# MS_Electron_SC.net
KiCad netlist of a schematic drawn in EAGLE
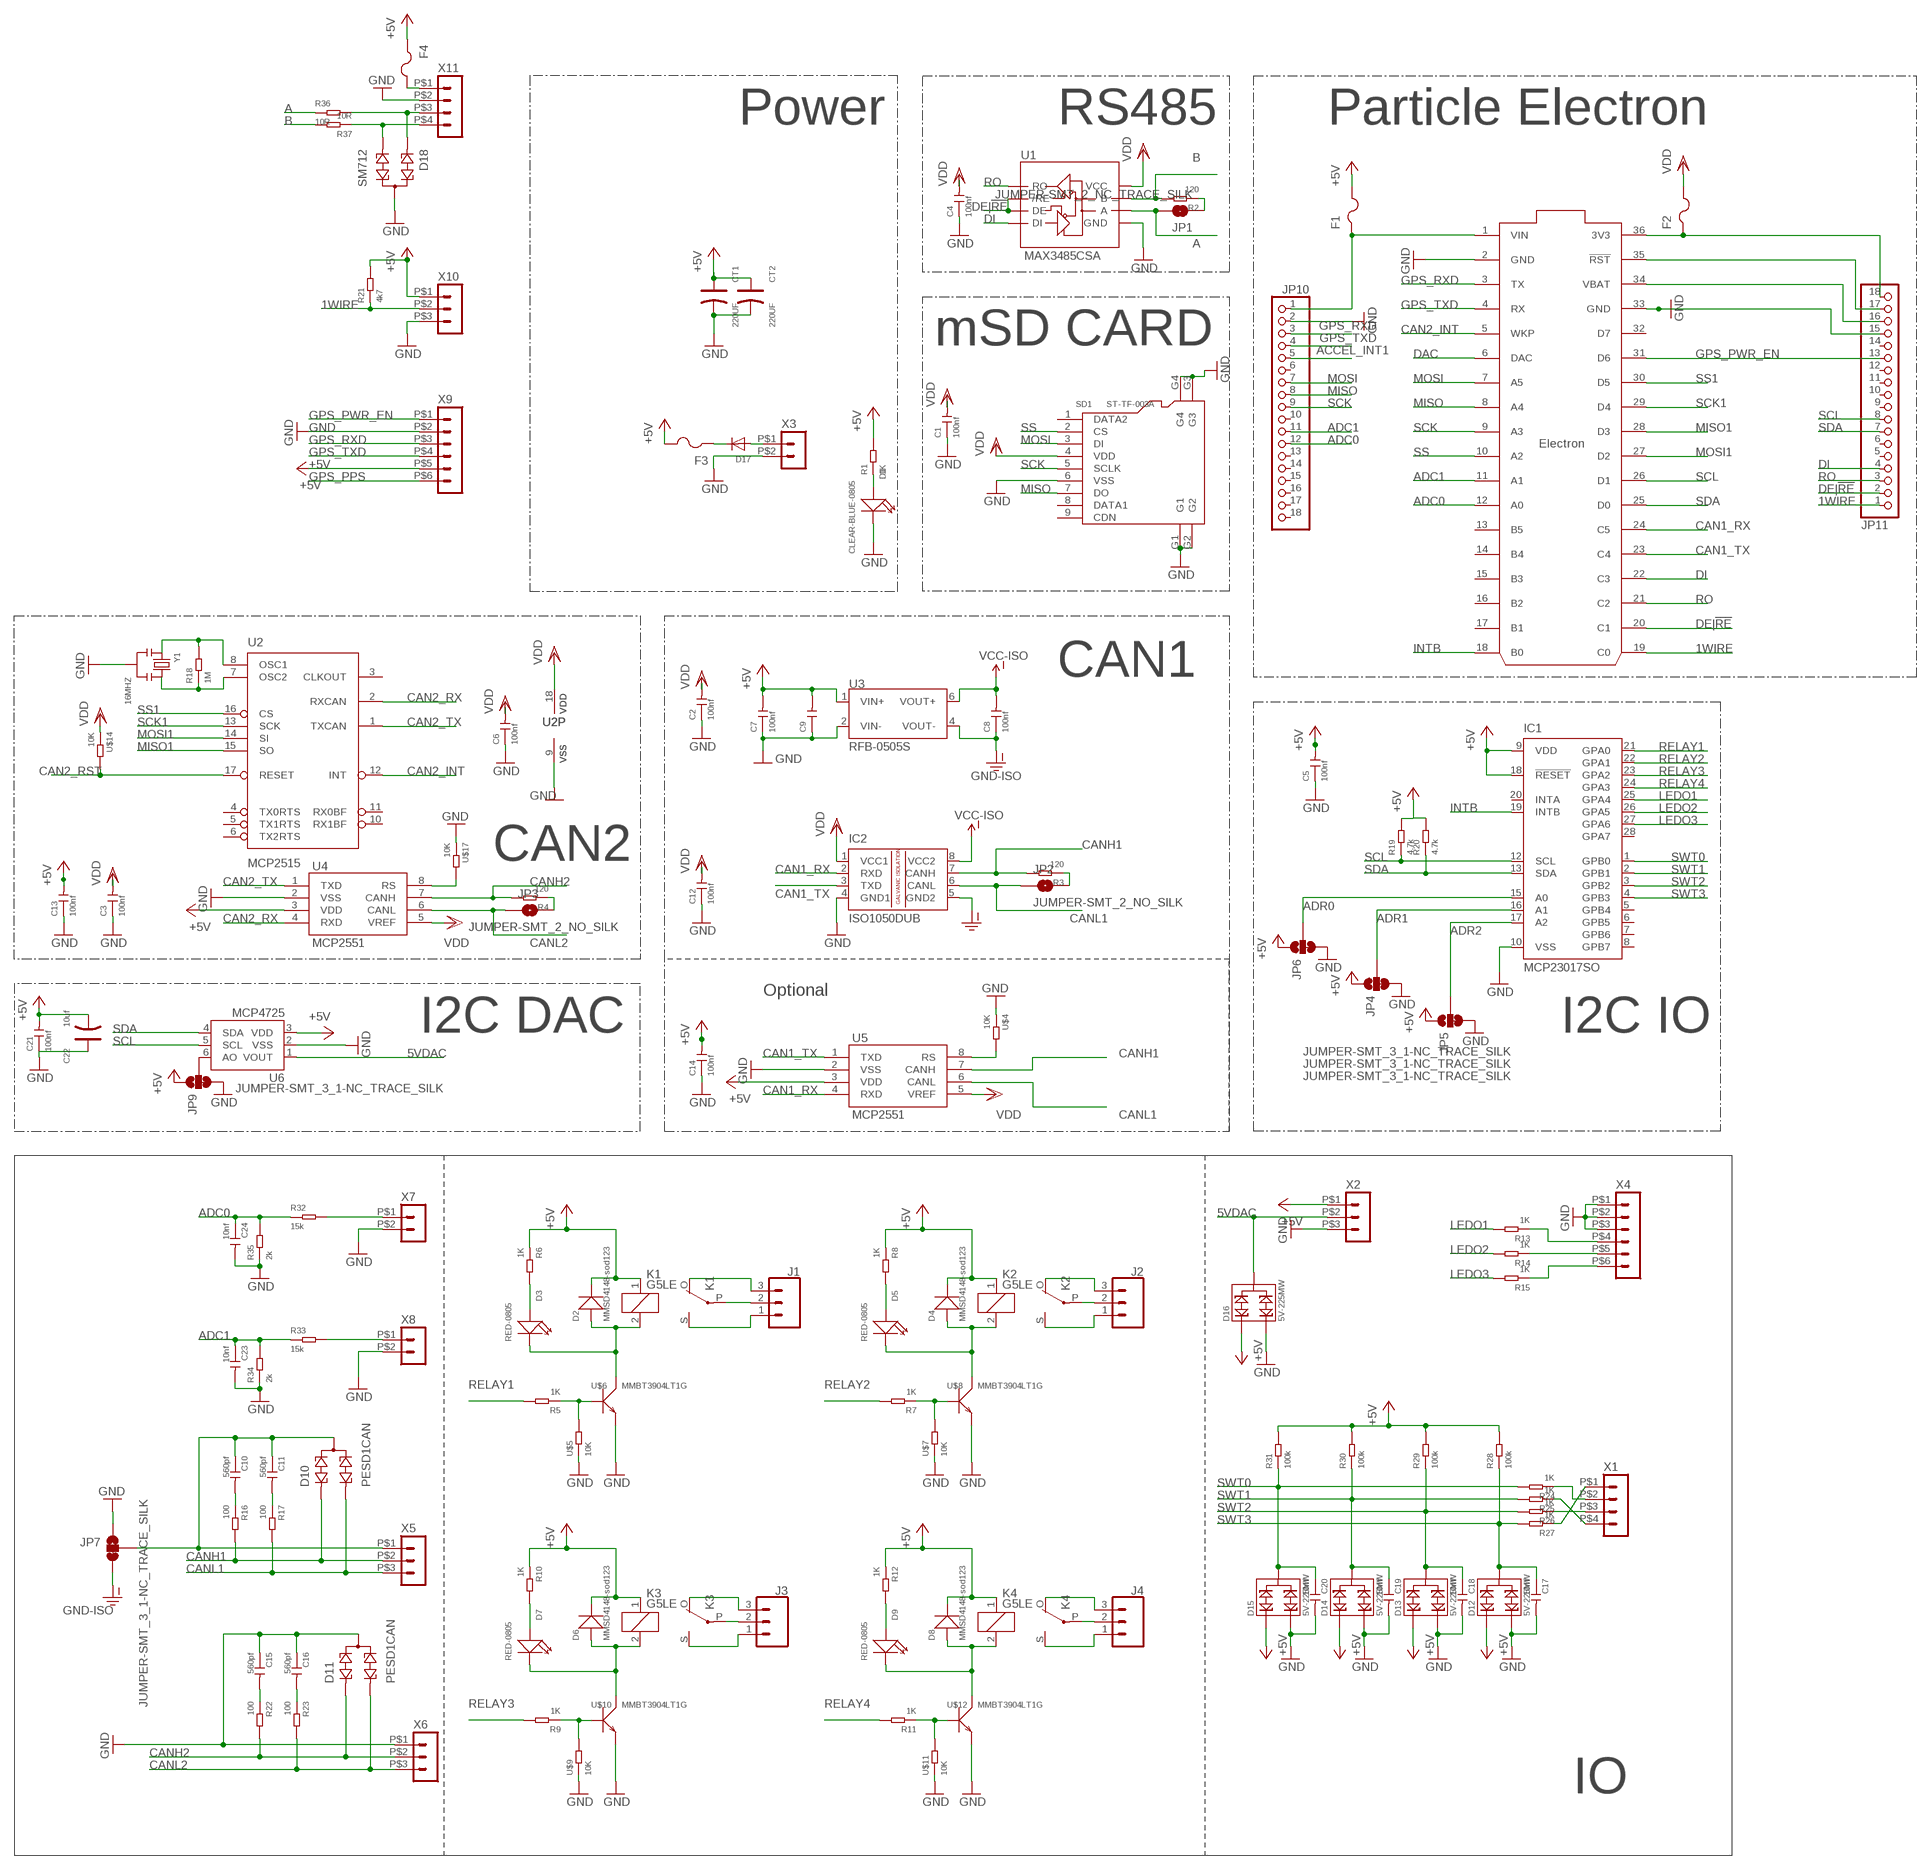
[diagram p0: schematic, sheet 1]

(export (version "E")
  (design (tool "Eeschema 10.0.6"))
  (components
    (comp (ref "C1")
      (value "100nf")
      (footprint "eagle-import:C0805")
      (fields (field (name "MPN") "CC0805KRX7R9BB104"))
      (libsource (lib "eagle-import") (part "CERAMIC-100NF-50V-10%-X7R(0805)"))
    )
    (comp (ref "C2")
      (value "100nf")
      (footprint "eagle-import:C0805")
      (fields (field (name "MPN") "CC0805KRX7R9BB104"))
      (libsource (lib "eagle-import") (part "CERAMIC-100NF-50V-10%-X7R(0805)"))
    )
    (comp (ref "C3")
      (value "100nf")
      (footprint "eagle-import:C0805")
      (fields (field (name "MPN") "CC0805KRX7R9BB104"))
      (libsource (lib "eagle-import") (part "CERAMIC-100NF-50V-10%-X7R(0805)"))
    )
    (comp (ref "C4")
      (value "100nf")
      (footprint "eagle-import:C0805")
      (fields (field (name "MPN") "CC0805KRX7R9BB104"))
      (libsource (lib "eagle-import") (part "CERAMIC-100NF-50V-10%-X7R(0805)"))
    )
    (comp (ref "C5")
      (value "100nf")
      (footprint "eagle-import:C0805")
      (fields (field (name "MPN") "CC0805KRX7R9BB104"))
      (libsource (lib "eagle-import") (part "CERAMIC-100NF-50V-10%-X7R(0805)"))
    )
    (comp (ref "C6")
      (value "100nf")
      (footprint "eagle-import:C0805")
      (fields (field (name "MPN") "CC0805KRX7R9BB104"))
      (libsource (lib "eagle-import") (part "CERAMIC-100NF-50V-10%-X7R(0805)"))
    )
    (comp (ref "C7")
      (value "100nf")
      (footprint "eagle-import:C0805")
      (fields (field (name "MPN") "CC0805KRX7R9BB104"))
      (libsource (lib "eagle-import") (part "CERAMIC-100NF-50V-10%-X7R(0805)"))
    )
    (comp (ref "C8")
      (value "100nf")
      (footprint "eagle-import:C0805")
      (fields (field (name "MPN") "CC0805KRX7R9BB104"))
      (libsource (lib "eagle-import") (part "CERAMIC-100NF-50V-10%-X7R(0805)"))
    )
    (comp (ref "C9")
      (value "CERAMIC-22UF-16V-10%-X7R(1206)")
      (footprint "eagle-import:C1206")
      (libsource (lib "eagle-import") (part "CERAMIC-22UF-16V-10%-X7R(1206)"))
    )
    (comp (ref "C10")
      (value "560pf")
      (footprint "eagle-import:C0805")
      (fields (field (name "MPN") "CC0805JRX7R9BB103"))
      (libsource (lib "eagle-import") (part "CERAMIC-10NF-50V-5%-X7R(0805)"))
    )
    (comp (ref "C11")
      (value "560pf")
      (footprint "eagle-import:C0805")
      (fields (field (name "MPN") "CC0805JRX7R9BB103"))
      (libsource (lib "eagle-import") (part "CERAMIC-10NF-50V-5%-X7R(0805)"))
    )
    (comp (ref "C12")
      (value "100nf")
      (footprint "eagle-import:C0805")
      (fields (field (name "MPN") "CC0805KRX7R9BB104"))
      (libsource (lib "eagle-import") (part "CERAMIC-100NF-50V-10%-X7R(0805)"))
    )
    (comp (ref "C13")
      (value "100nf")
      (footprint "eagle-import:C0805")
      (fields (field (name "MPN") "CC0805KRX7R9BB104"))
      (libsource (lib "eagle-import") (part "CERAMIC-100NF-50V-10%-X7R(0805)"))
    )
    (comp (ref "C14")
      (value "100nf")
      (footprint "eagle-import:C0805")
      (fields (field (name "MPN") "CC0805KRX7R9BB104"))
      (libsource (lib "eagle-import") (part "CERAMIC-100NF-50V-10%-X7R(0805)"))
    )
    (comp (ref "C15")
      (value "560pf")
      (footprint "eagle-import:C0805")
      (fields (field (name "MPN") "CC0805JRX7R9BB103"))
      (libsource (lib "eagle-import") (part "CERAMIC-10NF-50V-5%-X7R(0805)"))
    )
    (comp (ref "C16")
      (value "560pf")
      (footprint "eagle-import:C0805")
      (fields (field (name "MPN") "CC0805JRX7R9BB103"))
      (libsource (lib "eagle-import") (part "CERAMIC-10NF-50V-5%-X7R(0805)"))
    )
    (comp (ref "C17")
      (value "10nf")
      (footprint "eagle-import:C0805")
      (fields (field (name "MPN") "CC0805JRX7R9BB103"))
      (libsource (lib "eagle-import") (part "CERAMIC-10NF-50V-5%-X7R(0805)"))
    )
    (comp (ref "C18")
      (value "10nf")
      (footprint "eagle-import:C0805")
      (fields (field (name "MPN") "CC0805JRX7R9BB103"))
      (libsource (lib "eagle-import") (part "CERAMIC-10NF-50V-5%-X7R(0805)"))
    )
    (comp (ref "C19")
      (value "10nf")
      (footprint "eagle-import:C0805")
      (fields (field (name "MPN") "CC0805JRX7R9BB103"))
      (libsource (lib "eagle-import") (part "CERAMIC-10NF-50V-5%-X7R(0805)"))
    )
    (comp (ref "C20")
      (value "10nf")
      (footprint "eagle-import:C0805")
      (fields (field (name "MPN") "CC0805JRX7R9BB103"))
      (libsource (lib "eagle-import") (part "CERAMIC-10NF-50V-5%-X7R(0805)"))
    )
    (comp (ref "C21")
      (value "100nf")
      (footprint "eagle-import:C0805")
      (fields (field (name "MPN") "CC0805KRX7R9BB104"))
      (libsource (lib "eagle-import") (part "CERAMIC-100NF-50V-10%-X7R(0805)"))
    )
    (comp (ref "C22")
      (value "10uf")
      (footprint "eagle-import:AVX-A")
      (fields (field (name "MPN") "TAJA106K010RNJ"))
      (libsource (lib "eagle-import") (part "TANTALUM-SMD-10UF-10V-10%(AVX-A)"))
    )
    (comp (ref "C23")
      (value "10nf")
      (footprint "eagle-import:C0805")
      (fields (field (name "MPN") "CC0805JRX7R9BB103"))
      (libsource (lib "eagle-import") (part "CERAMIC-10NF-50V-5%-X7R(0805)"))
    )
    (comp (ref "C24")
      (value "10nf")
      (footprint "eagle-import:C0805")
      (fields (field (name "MPN") "CC0805JRX7R9BB103"))
      (libsource (lib "eagle-import") (part "CERAMIC-10NF-50V-5%-X7R(0805)"))
    )
    (comp (ref "CT1")
      (value "220UF")
      (footprint "eagle-import:ELECTRO-SMD-C-6MM")
      (fields (field (name "MPN") "CS1E221M-CRE77"))
      (libsource (lib "eagle-import") (part "ALUMINUM-SMD-220UF-16V(D6.3-H7.7MM)"))
    )
    (comp (ref "CT2")
      (value "220UF")
      (footprint "eagle-import:ELECTRO-SMD-C-6MM")
      (fields (field (name "MPN") "CS1E221M-CRE77"))
      (libsource (lib "eagle-import") (part "ALUMINUM-SMD-220UF-16V(D6.3-H7.7MM)"))
    )
    (comp (ref "D1")
      (value "CLEAR-BLUE-0805")
      (footprint "eagle-import:LED-0805")
      (fields (field (name "MPN") "EL-17-215/BHC-AN1P2/3T"))
      (libsource (lib "eagle-import") (part "SMD-LED-CLEAR-BLUE(0805)"))
    )
    (comp (ref "D2")
      (value "MMSD4148-sod123")
      (footprint "eagle-import:SOD-123")
      (fields (field (name "MPN") "MMSD4148"))
      (libsource (lib "eagle-import") (part "SMD-DIODE-100V-200MA(SOD-123)"))
    )
    (comp (ref "D3")
      (value "RED-0805")
      (footprint "eagle-import:LED-0805")
      (fields (field (name "MPN") "17-215SURC/S530-A2/TR8"))
      (libsource (lib "eagle-import") (part "SMD-LED-CLEAR-RED(0805)"))
    )
    (comp (ref "D4")
      (value "MMSD4148-sod123")
      (footprint "eagle-import:SOD-123")
      (fields (field (name "MPN") "MMSD4148"))
      (libsource (lib "eagle-import") (part "SMD-DIODE-100V-200MA(SOD-123)"))
    )
    (comp (ref "D5")
      (value "RED-0805")
      (footprint "eagle-import:LED-0805")
      (fields (field (name "MPN") "17-215SURC/S530-A2/TR8"))
      (libsource (lib "eagle-import") (part "SMD-LED-CLEAR-RED(0805)"))
    )
    (comp (ref "D6")
      (value "MMSD4148-sod123")
      (footprint "eagle-import:SOD-123")
      (fields (field (name "MPN") "MMSD4148"))
      (libsource (lib "eagle-import") (part "SMD-DIODE-100V-200MA(SOD-123)"))
    )
    (comp (ref "D7")
      (value "RED-0805")
      (footprint "eagle-import:LED-0805")
      (fields (field (name "MPN") "17-215SURC/S530-A2/TR8"))
      (libsource (lib "eagle-import") (part "SMD-LED-CLEAR-RED(0805)"))
    )
    (comp (ref "D8")
      (value "MMSD4148-sod123")
      (footprint "eagle-import:SOD-123")
      (fields (field (name "MPN") "MMSD4148"))
      (libsource (lib "eagle-import") (part "SMD-DIODE-100V-200MA(SOD-123)"))
    )
    (comp (ref "D9")
      (value "RED-0805")
      (footprint "eagle-import:LED-0805")
      (fields (field (name "MPN") "17-215SURC/S530-A2/TR8"))
      (libsource (lib "eagle-import") (part "SMD-LED-CLEAR-RED(0805)"))
    )
    (comp (ref "D10")
      (value "PESD1CAN")
      (footprint "eagle-import:SOT23")
      (libsource (lib "eagle-import") (part "PESD1CAN"))
    )
    (comp (ref "D11")
      (value "PESD1CAN")
      (footprint "eagle-import:SOT23")
      (libsource (lib "eagle-import") (part "PESD1CAN"))
    )
    (comp (ref "D12")
      (value "5V-225MW")
      (footprint "eagle-import:SOT-23")
      (fields (field (name "MPN") "CESD5V0AP"))
      (libsource (lib "eagle-import") (part "SMD-DIODE-TVS-5V-225MW(SOT-23)"))
    )
    (comp (ref "D13")
      (value "5V-225MW")
      (footprint "eagle-import:SOT-23")
      (fields (field (name "MPN") "CESD5V0AP"))
      (libsource (lib "eagle-import") (part "SMD-DIODE-TVS-5V-225MW(SOT-23)"))
    )
    (comp (ref "D14")
      (value "5V-225MW")
      (footprint "eagle-import:SOT-23")
      (fields (field (name "MPN") "CESD5V0AP"))
      (libsource (lib "eagle-import") (part "SMD-DIODE-TVS-5V-225MW(SOT-23)"))
    )
    (comp (ref "D15")
      (value "5V-225MW")
      (footprint "eagle-import:SOT-23")
      (fields (field (name "MPN") "CESD5V0AP"))
      (libsource (lib "eagle-import") (part "SMD-DIODE-TVS-5V-225MW(SOT-23)"))
    )
    (comp (ref "D16")
      (value "5V-225MW")
      (footprint "eagle-import:SOT-23")
      (fields (field (name "MPN") "CESD5V0AP"))
      (libsource (lib "eagle-import") (part "SMD-DIODE-TVS-5V-225MW(SOT-23)"))
    )
    (comp (ref "D17")
      (value "DIODESMA")
      (footprint "eagle-import:SMADIODE")
      (libsource (lib "eagle-import") (part "DIODESMA"))
    )
    (comp (ref "D18")
      (value "SM712")
      (footprint "eagle-import:SOT23")
      (libsource (lib "eagle-import") (part "PESD1CAN"))
    )
    (comp (ref "F1")
      (value "PTCFUSE-1812")
      (footprint "eagle-import:1812")
      (libsource (lib "eagle-import") (part "PTCFUSE-1812"))
    )
    (comp (ref "F2")
      (value "PTCFUSE-1812")
      (footprint "eagle-import:1812")
      (libsource (lib "eagle-import") (part "PTCFUSE-1812"))
    )
    (comp (ref "F3")
      (value "PTCFUSE-1812")
      (footprint "eagle-import:1812")
      (libsource (lib "eagle-import") (part "PTCFUSE-1812"))
    )
    (comp (ref "F4")
      (value "PTCFUSE-1812")
      (footprint "eagle-import:1812")
      (libsource (lib "eagle-import") (part "PTCFUSE-1812"))
    )
    (comp (ref "IC1")
      (value "MCP23017SO")
      (footprint "eagle-import:SO28W")
      (libsource (lib "eagle-import") (part "MCP23017SO"))
    )
    (comp (ref "IC2")
      (value "ISO1050DUB")
      (footprint "eagle-import:DUB-R-PDSO-G8")
      (fields (field (name "MPN") "ISO1050DUBR"))
      (libsource (lib "eagle-import") (part "ISO1050DUB"))
    )
    (comp (ref "J1")
      (value "CONN_03SCREW")
      (footprint "eagle-import:SCREWTERMINAL-3.5MM-3")
      (libsource (lib "eagle-import") (part "CONN_03SCREW"))
    )
    (comp (ref "J2")
      (value "CONN_03SCREW")
      (footprint "eagle-import:SCREWTERMINAL-3.5MM-3")
      (libsource (lib "eagle-import") (part "CONN_03SCREW"))
    )
    (comp (ref "J3")
      (value "CONN_03SCREW")
      (footprint "eagle-import:SCREWTERMINAL-3.5MM-3")
      (libsource (lib "eagle-import") (part "CONN_03SCREW"))
    )
    (comp (ref "J4")
      (value "CONN_03SCREW")
      (footprint "eagle-import:SCREWTERMINAL-3.5MM-3")
      (libsource (lib "eagle-import") (part "CONN_03SCREW"))
    )
    (comp (ref "JP1")
      (value "JUMPER-SMT_2_NC_TRACE_SILK")
      (footprint "eagle-import:SMT-JUMPER_2_NC_TRACE_SILK")
      (libsource (lib "eagle-import") (part "JUMPER-SMT_2_NC_TRACE_SILK"))
    )
    (comp (ref "JP2")
      (value "JUMPER-SMT_2_NO_SILK")
      (footprint "eagle-import:SMT-JUMPER_2_NO_SILK")
      (libsource (lib "eagle-import") (part "JUMPER-SMT_2_NO_SILK"))
    )
    (comp (ref "JP3")
      (value "JUMPER-SMT_2_NO_SILK")
      (footprint "eagle-import:SMT-JUMPER_2_NO_SILK")
      (libsource (lib "eagle-import") (part "JUMPER-SMT_2_NO_SILK"))
    )
    (comp (ref "JP4")
      (value "JUMPER-SMT_3_1-NC_TRACE_SILK")
      (footprint "eagle-import:SMT-JUMPER_3_1-NC_TRACE_SILK")
      (libsource (lib "eagle-import") (part "JUMPER-SMT_3_1-NC_TRACE_SILK"))
    )
    (comp (ref "JP5")
      (value "JUMPER-SMT_3_1-NC_TRACE_SILK")
      (footprint "eagle-import:SMT-JUMPER_3_1-NC_TRACE_SILK")
      (libsource (lib "eagle-import") (part "JUMPER-SMT_3_1-NC_TRACE_SILK"))
    )
    (comp (ref "JP6")
      (value "JUMPER-SMT_3_1-NC_TRACE_SILK")
      (footprint "eagle-import:SMT-JUMPER_3_1-NC_TRACE_SILK")
      (libsource (lib "eagle-import") (part "JUMPER-SMT_3_1-NC_TRACE_SILK"))
    )
    (comp (ref "JP7")
      (value "JUMPER-SMT_3_1-NC_TRACE_SILK")
      (footprint "eagle-import:SMT-JUMPER_3_1-NC_TRACE_SILK")
      (libsource (lib "eagle-import") (part "JUMPER-SMT_3_1-NC_TRACE_SILK"))
    )
    (comp (ref "JP9")
      (value "JUMPER-SMT_3_1-NC_TRACE_SILK")
      (footprint "eagle-import:SMT-JUMPER_3_1-NC_TRACE_SILK")
      (libsource (lib "eagle-import") (part "JUMPER-SMT_3_1-NC_TRACE_SILK"))
    )
    (comp (ref "JP10")
      (value "PINHD-1X18-BIG")
      (footprint "eagle-import:1X18-BIG")
      (libsource (lib "eagle-import") (part "PINHD-1X18-BIG"))
    )
    (comp (ref "JP11")
      (value "PINHD-1X18-BIG")
      (footprint "eagle-import:1X18-BIG")
      (libsource (lib "eagle-import") (part "PINHD-1X18-BIG"))
    )
    (comp (ref "K1")
      (value "G5LE")
      (footprint "eagle-import:G5LE")
      (libsource (lib "eagle-import") (part "G5LE"))
    )
    (comp (ref "K2")
      (value "G5LE")
      (footprint "eagle-import:G5LE")
      (libsource (lib "eagle-import") (part "G5LE"))
    )
    (comp (ref "K3")
      (value "G5LE")
      (footprint "eagle-import:G5LE")
      (libsource (lib "eagle-import") (part "G5LE"))
    )
    (comp (ref "K4")
      (value "G5LE")
      (footprint "eagle-import:G5LE")
      (libsource (lib "eagle-import") (part "G5LE"))
    )
    (comp (ref "R1")
      (value "1K")
      (footprint "eagle-import:R0805")
      (fields (field (name "MPN") "RC0805JR-071KL"))
      (libsource (lib "eagle-import") (part "SMD-RES-1K-5%-1/8W(0805)"))
    )
    (comp (ref "R2")
      (value "120")
      (footprint "eagle-import:R0805")
      (fields (field (name "MPN") "RC0805JR-071KL"))
      (libsource (lib "eagle-import") (part "SMD-RES-120R-1%-1/8W(0805)"))
    )
    (comp (ref "R3")
      (value "120")
      (footprint "eagle-import:R0805")
      (fields (field (name "MPN") "RC0805JR-071KL"))
      (libsource (lib "eagle-import") (part "SMD-RES-120R-1%-1/8W(0805)"))
    )
    (comp (ref "R4")
      (value "120")
      (footprint "eagle-import:R0805")
      (fields (field (name "MPN") "RC0805JR-071KL"))
      (libsource (lib "eagle-import") (part "SMD-RES-120R-1%-1/8W(0805)"))
    )
    (comp (ref "R5")
      (value "1K")
      (footprint "eagle-import:R0805")
      (fields (field (name "MPN") "RC0805JR-071KL"))
      (libsource (lib "eagle-import") (part "SMD-RES-1K-5%-1/8W(0805)"))
    )
    (comp (ref "R6")
      (value "1K")
      (footprint "eagle-import:R0805")
      (fields (field (name "MPN") "RC0805JR-071KL"))
      (libsource (lib "eagle-import") (part "SMD-RES-1K-5%-1/8W(0805)"))
    )
    (comp (ref "R7")
      (value "1K")
      (footprint "eagle-import:R0805")
      (fields (field (name "MPN") "RC0805JR-071KL"))
      (libsource (lib "eagle-import") (part "SMD-RES-1K-5%-1/8W(0805)"))
    )
    (comp (ref "R8")
      (value "1K")
      (footprint "eagle-import:R0805")
      (fields (field (name "MPN") "RC0805JR-071KL"))
      (libsource (lib "eagle-import") (part "SMD-RES-1K-5%-1/8W(0805)"))
    )
    (comp (ref "R9")
      (value "1K")
      (footprint "eagle-import:R0805")
      (fields (field (name "MPN") "RC0805JR-071KL"))
      (libsource (lib "eagle-import") (part "SMD-RES-1K-5%-1/8W(0805)"))
    )
    (comp (ref "R10")
      (value "1K")
      (footprint "eagle-import:R0805")
      (fields (field (name "MPN") "RC0805JR-071KL"))
      (libsource (lib "eagle-import") (part "SMD-RES-1K-5%-1/8W(0805)"))
    )
    (comp (ref "R11")
      (value "1K")
      (footprint "eagle-import:R0805")
      (fields (field (name "MPN") "RC0805JR-071KL"))
      (libsource (lib "eagle-import") (part "SMD-RES-1K-5%-1/8W(0805)"))
    )
    (comp (ref "R12")
      (value "1K")
      (footprint "eagle-import:R0805")
      (fields (field (name "MPN") "RC0805JR-071KL"))
      (libsource (lib "eagle-import") (part "SMD-RES-1K-5%-1/8W(0805)"))
    )
    (comp (ref "R13")
      (value "1K")
      (footprint "eagle-import:R0805")
      (fields (field (name "MPN") "RC0805JR-071KL"))
      (libsource (lib "eagle-import") (part "SMD-RES-1K-5%-1/8W(0805)"))
    )
    (comp (ref "R14")
      (value "1K")
      (footprint "eagle-import:R0805")
      (fields (field (name "MPN") "RC0805JR-071KL"))
      (libsource (lib "eagle-import") (part "SMD-RES-1K-5%-1/8W(0805)"))
    )
    (comp (ref "R15")
      (value "1K")
      (footprint "eagle-import:R0805")
      (fields (field (name "MPN") "RC0805JR-071KL"))
      (libsource (lib "eagle-import") (part "SMD-RES-1K-5%-1/8W(0805)"))
    )
    (comp (ref "R16")
      (value "100")
      (footprint "eagle-import:R0805")
      (fields (field (name "MPN") "RC0805JR-071KL"))
      (libsource (lib "eagle-import") (part "SMD-RES-100R-1%-1/8W(0805)"))
    )
    (comp (ref "R17")
      (value "100")
      (footprint "eagle-import:R0805")
      (fields (field (name "MPN") "RC0805JR-071KL"))
      (libsource (lib "eagle-import") (part "SMD-RES-100R-1%-1/8W(0805)"))
    )
    (comp (ref "R18")
      (value "1M")
      (footprint "eagle-import:R0805")
      (fields (field (name "MPN") "RC0805JR-071KL"))
      (libsource (lib "eagle-import") (part "SMD-RES-1M-1%-1/8W(0805)"))
    )
    (comp (ref "R19")
      (value "4.7k")
      (footprint "eagle-import:R0805")
      (fields (field (name "MPN") "RC0805JR-071KL"))
      (libsource (lib "eagle-import") (part "SMD-RES-4.7K-1%-1/8W(0805)"))
    )
    (comp (ref "R20")
      (value "4.7k")
      (footprint "eagle-import:R0805")
      (fields (field (name "MPN") "RC0805JR-071KL"))
      (libsource (lib "eagle-import") (part "SMD-RES-4.7K-1%-1/8W(0805)"))
    )
    (comp (ref "R21")
      (value "4k7")
      (footprint "eagle-import:R0805")
      (fields (field (name "MPN") "RC0805JR-071KL"))
      (libsource (lib "eagle-import") (part "SMD-RES-4.7K-1%-1/8W(0805)"))
    )
    (comp (ref "R22")
      (value "100")
      (footprint "eagle-import:R0805")
      (fields (field (name "MPN") "RC0805JR-071KL"))
      (libsource (lib "eagle-import") (part "SMD-RES-100R-1%-1/8W(0805)"))
    )
    (comp (ref "R23")
      (value "100")
      (footprint "eagle-import:R0805")
      (fields (field (name "MPN") "RC0805JR-071KL"))
      (libsource (lib "eagle-import") (part "SMD-RES-100R-1%-1/8W(0805)"))
    )
    (comp (ref "R24")
      (value "1K")
      (footprint "eagle-import:R0805")
      (fields (field (name "MPN") "RC0805JR-071KL"))
      (libsource (lib "eagle-import") (part "SMD-RES-1K-5%-1/8W(0805)"))
    )
    (comp (ref "R25")
      (value "1K")
      (footprint "eagle-import:R0805")
      (fields (field (name "MPN") "RC0805JR-071KL"))
      (libsource (lib "eagle-import") (part "SMD-RES-1K-5%-1/8W(0805)"))
    )
    (comp (ref "R26")
      (value "1K")
      (footprint "eagle-import:R0805")
      (fields (field (name "MPN") "RC0805JR-071KL"))
      (libsource (lib "eagle-import") (part "SMD-RES-1K-5%-1/8W(0805)"))
    )
    (comp (ref "R27")
      (value "1K")
      (footprint "eagle-import:R0805")
      (fields (field (name "MPN") "RC0805JR-071KL"))
      (libsource (lib "eagle-import") (part "SMD-RES-1K-5%-1/8W(0805)"))
    )
    (comp (ref "R28")
      (value "100k")
      (footprint "eagle-import:R0805")
      (fields (field (name "MPN") "RC0805JR-071KL"))
      (libsource (lib "eagle-import") (part "SMD-RES-100K-1%-1/8W(0805)"))
    )
    (comp (ref "R29")
      (value "100k")
      (footprint "eagle-import:R0805")
      (fields (field (name "MPN") "RC0805JR-071KL"))
      (libsource (lib "eagle-import") (part "SMD-RES-100K-1%-1/8W(0805)"))
    )
    (comp (ref "R30")
      (value "100k")
      (footprint "eagle-import:R0805")
      (fields (field (name "MPN") "RC0805JR-071KL"))
      (libsource (lib "eagle-import") (part "SMD-RES-100K-1%-1/8W(0805)"))
    )
    (comp (ref "R31")
      (value "100k")
      (footprint "eagle-import:R0805")
      (fields (field (name "MPN") "RC0805JR-071KL"))
      (libsource (lib "eagle-import") (part "SMD-RES-100K-1%-1/8W(0805)"))
    )
    (comp (ref "R32")
      (value "15k")
      (footprint "eagle-import:R0805")
      (fields (field (name "MPN") "RC0805JR-071KL"))
      (libsource (lib "eagle-import") (part "SMD-RES-15K-5%-1/8W(0805)"))
    )
    (comp (ref "R33")
      (value "15k")
      (footprint "eagle-import:R0805")
      (fields (field (name "MPN") "RC0805JR-071KL"))
      (libsource (lib "eagle-import") (part "SMD-RES-15K-5%-1/8W(0805)"))
    )
    (comp (ref "R34")
      (value "2k")
      (footprint "eagle-import:R0805")
      (fields (field (name "MPN") "RC0805JR-071KL"))
      (libsource (lib "eagle-import") (part "SMD-RES-2K-1%-1/8W(0805)"))
    )
    (comp (ref "R35")
      (value "2k")
      (footprint "eagle-import:R0805")
      (fields (field (name "MPN") "RC0805JR-071KL"))
      (libsource (lib "eagle-import") (part "SMD-RES-2K-1%-1/8W(0805)"))
    )
    (comp (ref "R36")
      (value "10R")
      (footprint "eagle-import:R0805")
      (fields (field (name "MPN") "RC0805JR-071KL"))
      (libsource (lib "eagle-import") (part "SMD-RES-4.7K-1%-1/8W(0805)"))
    )
    (comp (ref "R37")
      (value "10R")
      (footprint "eagle-import:R0805")
      (fields (field (name "MPN") "RC0805JR-071KL"))
      (libsource (lib "eagle-import") (part "SMD-RES-4.7K-1%-1/8W(0805)"))
    )
    (comp (ref "SD1")
      (value "ST-TF-003A")
      (footprint "eagle-import:MICRO-SD9+4P-SMD-16.1X14.5X1.85MM")
      (libsource (lib "eagle-import") (part "MICRO-SD-CARD-SOCKET-9P(ST-TF-003A)"))
    )
    (comp (ref "U$1")
      (value "ELECTRON_WITH_HEADERS")
      (footprint "eagle-import:ELECTRON")
      (libsource (lib "eagle-import") (part "ELECTRON_WITH_HEADERS"))
    )
    (comp (ref "U$4")
      (value "10K")
      (footprint "eagle-import:R0805")
      (fields (field (name "MPN") "RC0805FR-0710KL"))
      (libsource (lib "eagle-import") (part "SMD-RES-10K-1%-1/8W(0805)"))
    )
    (comp (ref "U$5")
      (value "10K")
      (footprint "eagle-import:R0805")
      (fields (field (name "MPN") "RC0805FR-0710KL"))
      (libsource (lib "eagle-import") (part "SMD-RES-10K-1%-1/8W(0805)"))
    )
    (comp (ref "U$6")
      (value "MMBT3904LT1G")
      (footprint "eagle-import:SOT-23")
      (libsource (lib "eagle-import") (part "SMD-TRANSISTORS-NPN-40V-200MA-MMBT3904LT1G(SOT-23)"))
    )
    (comp (ref "U$7")
      (value "10K")
      (footprint "eagle-import:R0805")
      (fields (field (name "MPN") "RC0805FR-0710KL"))
      (libsource (lib "eagle-import") (part "SMD-RES-10K-1%-1/8W(0805)"))
    )
    (comp (ref "U$8")
      (value "MMBT3904LT1G")
      (footprint "eagle-import:SOT-23")
      (libsource (lib "eagle-import") (part "SMD-TRANSISTORS-NPN-40V-200MA-MMBT3904LT1G(SOT-23)"))
    )
    (comp (ref "U$9")
      (value "10K")
      (footprint "eagle-import:R0805")
      (fields (field (name "MPN") "RC0805FR-0710KL"))
      (libsource (lib "eagle-import") (part "SMD-RES-10K-1%-1/8W(0805)"))
    )
    (comp (ref "U$10")
      (value "MMBT3904LT1G")
      (footprint "eagle-import:SOT-23")
      (libsource (lib "eagle-import") (part "SMD-TRANSISTORS-NPN-40V-200MA-MMBT3904LT1G(SOT-23)"))
    )
    (comp (ref "U$11")
      (value "10K")
      (footprint "eagle-import:R0805")
      (fields (field (name "MPN") "RC0805FR-0710KL"))
      (libsource (lib "eagle-import") (part "SMD-RES-10K-1%-1/8W(0805)"))
    )
    (comp (ref "U$12")
      (value "MMBT3904LT1G")
      (footprint "eagle-import:SOT-23")
      (libsource (lib "eagle-import") (part "SMD-TRANSISTORS-NPN-40V-200MA-MMBT3904LT1G(SOT-23)"))
    )
    (comp (ref "U$14")
      (value "10K")
      (footprint "eagle-import:R0805")
      (fields (field (name "MPN") "RC0805FR-0710KL"))
      (libsource (lib "eagle-import") (part "SMD-RES-10K-1%-1/8W(0805)"))
    )
    (comp (ref "U$17")
      (value "10K")
      (footprint "eagle-import:R0805")
      (fields (field (name "MPN") "RC0805FR-0710KL"))
      (libsource (lib "eagle-import") (part "SMD-RES-10K-1%-1/8W(0805)"))
    )
    (comp (ref "U1")
      (value "MAX3485CSA")
      (footprint "eagle-import:SO08")
      (libsource (lib "eagle-import") (part "RS485SOIC"))
    )
    (comp (ref "U2")
      (value "MCP2515")
      (footprint "eagle-import:SO18W")
      (libsource (lib "eagle-import") (part "MCP2515(MCP2510)SO"))
    )
    (comp (ref "U3")
      (value "RFB-0505S")
      (footprint "eagle-import:RFB-0505S")
      (libsource (lib "eagle-import") (part "RFB-0505S"))
    )
    (comp (ref "U4")
      (value "MCP2551")
      (footprint "eagle-import:SO08")
      (libsource (lib "eagle-import") (part "MCP2551"))
    )
    (comp (ref "U5")
      (value "MCP2551")
      (footprint "eagle-import:SO08")
      (libsource (lib "eagle-import") (part "MCP2551"))
    )
    (comp (ref "U6")
      (value "MCP4725")
      (footprint "eagle-import:SOT23-6")
      (libsource (lib "eagle-import") (part "MCP4725SOT-23"))
    )
    (comp (ref "X1")
      (value "HEADER_POS4_43045-0401")
      (footprint "eagle-import:43045-0400")
      (libsource (lib "eagle-import") (part "HEADER_POS4_?43045-0401"))
    )
    (comp (ref "X2")
      (value "HEADER_POS3_43650-0300")
      (footprint "eagle-import:43650-0300")
      (libsource (lib "eagle-import") (part "HEADER_POS3_?43650-0300"))
    )
    (comp (ref "X3")
      (value "HEADER_POS2_43650-0200")
      (footprint "eagle-import:43650-0200")
      (libsource (lib "eagle-import") (part "HEADER_POS2_?43650-0200"))
    )
    (comp (ref "X4")
      (value "HEADER_POS6_43045-0600")
      (footprint "eagle-import:43045-0600")
      (libsource (lib "eagle-import") (part "HEADER_POS6_?43045-0600"))
    )
    (comp (ref "X5")
      (value "HEADER_POS3_43650-0300")
      (footprint "eagle-import:43650-0300")
      (libsource (lib "eagle-import") (part "HEADER_POS3_?43650-0300"))
    )
    (comp (ref "X6")
      (value "HEADER_POS3_43650-0300")
      (footprint "eagle-import:43650-0300")
      (libsource (lib "eagle-import") (part "HEADER_POS3_?43650-0300"))
    )
    (comp (ref "X7")
      (value "HEADER_POS2_43650-0200")
      (footprint "eagle-import:43650-0200")
      (libsource (lib "eagle-import") (part "HEADER_POS2_?43650-0200"))
    )
    (comp (ref "X8")
      (value "HEADER_POS2_43650-0200")
      (footprint "eagle-import:43650-0200")
      (libsource (lib "eagle-import") (part "HEADER_POS2_?43650-0200"))
    )
    (comp (ref "X9")
      (value "HEADER_POS6_43045-0600")
      (footprint "eagle-import:43045-0600")
      (libsource (lib "eagle-import") (part "HEADER_POS6_?43045-0600"))
    )
    (comp (ref "X10")
      (value "HEADER_POS3_43650-0300")
      (footprint "eagle-import:43650-0300")
      (libsource (lib "eagle-import") (part "HEADER_POS3_?43650-0300"))
    )
    (comp (ref "X11")
      (value "HEADER_POS4_43045-0401")
      (footprint "eagle-import:43045-0400")
      (libsource (lib "eagle-import") (part "HEADER_POS4_?43045-0401"))
    )
    (comp (ref "Y1")
      (value "16MHZ")
      (footprint "eagle-import:X3-SMD-3.6X1.3X0.8MM")
      (fields (field (name "MPN") "CSTCE16M0V53-R0"))
      (libsource (lib "eagle-import") (part "SMD-RESONATOR-16MHZ-15PF-0.5%-40R(3P-3.2X1.3MM)"))
    )
  )
  (nets
    (net (code "1") (name "+5V") (class "Default")
      (node (ref "C13") (pin "2") (pinfunction "2_2") (pintype "passive"))
      (node (ref "C14") (pin "2") (pinfunction "2_2") (pintype "passive"))
      (node (ref "C21") (pin "2") (pinfunction "2_2") (pintype "passive"))
      (node (ref "C22") (pin "-") (pinfunction "-_-") (pintype "passive"))
      (node (ref "C5") (pin "2") (pinfunction "2_2") (pintype "passive"))
      (node (ref "C7") (pin "2") (pinfunction "2_2") (pintype "passive"))
      (node (ref "C9") (pin "2") (pinfunction "2_2") (pintype "passive"))
      (node (ref "CT1") (pin "+") (pinfunction "+_+") (pintype "passive"))
      (node (ref "CT2") (pin "+") (pinfunction "+_+") (pintype "passive"))
      (node (ref "D12") (pin "1") (pinfunction "1_1") (pintype "power_in"))
      (node (ref "D13") (pin "1") (pinfunction "1_1") (pintype "power_in"))
      (node (ref "D14") (pin "1") (pinfunction "1_1") (pintype "power_in"))
      (node (ref "D15") (pin "1") (pinfunction "1_1") (pintype "power_in"))
      (node (ref "D16") (pin "1") (pinfunction "1_1") (pintype "power_in"))
      (node (ref "D2") (pin "-") (pinfunction "-_-") (pintype "passive"))
      (node (ref "D4") (pin "-") (pinfunction "-_-") (pintype "passive"))
      (node (ref "D6") (pin "-") (pinfunction "-_-") (pintype "passive"))
      (node (ref "D8") (pin "-") (pinfunction "-_-") (pintype "passive"))
      (node (ref "F1") (pin "2") (pinfunction "2_2") (pintype "passive"))
      (node (ref "F3") (pin "2") (pinfunction "2_2") (pintype "passive"))
      (node (ref "F4") (pin "1") (pinfunction "1_1") (pintype "passive"))
      (node (ref "IC1") (pin "18") (pinfunction "~{RESET}_18") (pintype "input"))
      (node (ref "IC1") (pin "9") (pinfunction "VDD_9") (pintype "power_in"))
      (node (ref "JP4") (pin "1") (pinfunction "1_1") (pintype "passive"))
      (node (ref "JP5") (pin "1") (pinfunction "1_1") (pintype "passive"))
      (node (ref "JP6") (pin "1") (pinfunction "1_1") (pintype "passive"))
      (node (ref "JP9") (pin "1") (pinfunction "1_1") (pintype "passive"))
      (node (ref "K1") (pin "1") (pinfunction "1_1") (pintype "passive"))
      (node (ref "K2") (pin "1") (pinfunction "1_1") (pintype "passive"))
      (node (ref "K3") (pin "1") (pinfunction "1_1") (pintype "passive"))
      (node (ref "K4") (pin "1") (pinfunction "1_1") (pintype "passive"))
      (node (ref "R1") (pin "2") (pinfunction "2_2") (pintype "passive"))
      (node (ref "R10") (pin "1") (pinfunction "1_1") (pintype "passive"))
      (node (ref "R12") (pin "1") (pinfunction "1_1") (pintype "passive"))
      (node (ref "R19") (pin "2") (pinfunction "2_2") (pintype "passive"))
      (node (ref "R20") (pin "2") (pinfunction "2_2") (pintype "passive"))
      (node (ref "R21") (pin "2") (pinfunction "2_2") (pintype "passive"))
      (node (ref "R28") (pin "2") (pinfunction "2_2") (pintype "passive"))
      (node (ref "R29") (pin "2") (pinfunction "2_2") (pintype "passive"))
      (node (ref "R30") (pin "2") (pinfunction "2_2") (pintype "passive"))
      (node (ref "R31") (pin "2") (pinfunction "2_2") (pintype "passive"))
      (node (ref "R6") (pin "1") (pinfunction "1_1") (pintype "passive"))
      (node (ref "R8") (pin "1") (pinfunction "1_1") (pintype "passive"))
      (node (ref "U3") (pin "1") (pinfunction "VIN+_1") (pintype "bidirectional"))
      (node (ref "U4") (pin "3") (pinfunction "VDD_3") (pintype "bidirectional"))
      (node (ref "U5") (pin "3") (pinfunction "VDD_3") (pintype "bidirectional"))
      (node (ref "U6") (pin "3") (pinfunction "VDD_3") (pintype "bidirectional"))
      (node (ref "X10") (pin "P$1") (pinfunction "1_P$1") (pintype "passive"))
      (node (ref "X2") (pin "P$1") (pinfunction "1_P$1") (pintype "passive"))
      (node (ref "X9") (pin "P$5") (pinfunction "5_P$5") (pintype "passive"))
    )
    (net (code "2") (name "/1WIRE") (class "Default")
      (node (ref "JP11") (pin "1") (pinfunction "1_1") (pintype "passive"))
      (node (ref "R21") (pin "1") (pinfunction "1_1") (pintype "passive"))
      (node (ref "U$1") (pin "19") (pinfunction "C0_19") (pintype "bidirectional"))
      (node (ref "X10") (pin "P$2") (pinfunction "2_P$2") (pintype "passive"))
    )
    (net (code "3") (name "/5VDAC") (class "Default")
      (node (ref "D16") (pin "3") (pinfunction "3_3") (pintype "bidirectional"))
      (node (ref "U6") (pin "1") (pinfunction "VOUT_1") (pintype "bidirectional"))
      (node (ref "X2") (pin "P$2") (pinfunction "2_P$2") (pintype "passive"))
    )
    (net (code "4") (name "/A") (class "Default")
      (node (ref "JP1") (pin "2") (pinfunction "2_2") (pintype "passive"))
      (node (ref "R36") (pin "1") (pinfunction "1_1") (pintype "passive"))
      (node (ref "U1") (pin "6") (pinfunction "A_6") (pintype "bidirectional"))
    )
    (net (code "5") (name "/ACCEL_INT1") (class "Default")
      (node (ref "JP10") (pin "5") (pinfunction "5_5") (pintype "passive"))
    )
    (net (code "6") (name "/ADC0") (class "Default")
      (node (ref "C24") (pin "1") (pinfunction "1_1") (pintype "passive"))
      (node (ref "JP10") (pin "12") (pinfunction "12_12") (pintype "passive"))
      (node (ref "R32") (pin "1") (pinfunction "1_1") (pintype "passive"))
      (node (ref "R35") (pin "2") (pinfunction "2_2") (pintype "passive"))
      (node (ref "U$1") (pin "12") (pinfunction "A0_12") (pintype "bidirectional"))
    )
    (net (code "7") (name "/ADC1") (class "Default")
      (node (ref "C23") (pin "1") (pinfunction "1_1") (pintype "passive"))
      (node (ref "JP10") (pin "11") (pinfunction "11_11") (pintype "passive"))
      (node (ref "R33") (pin "1") (pinfunction "1_1") (pintype "passive"))
      (node (ref "R34") (pin "2") (pinfunction "2_2") (pintype "passive"))
      (node (ref "U$1") (pin "11") (pinfunction "A1_11") (pintype "bidirectional"))
    )
    (net (code "8") (name "/ADR0") (class "Default")
      (node (ref "IC1") (pin "15") (pinfunction "A0_15") (pintype "input"))
      (node (ref "JP6") (pin "2") (pinfunction "2_2") (pintype "passive"))
    )
    (net (code "9") (name "/ADR1") (class "Default")
      (node (ref "IC1") (pin "16") (pinfunction "A1_16") (pintype "input"))
      (node (ref "JP4") (pin "2") (pinfunction "2_2") (pintype "passive"))
    )
    (net (code "10") (name "/ADR2") (class "Default")
      (node (ref "IC1") (pin "17") (pinfunction "A2_17") (pintype "input"))
      (node (ref "JP5") (pin "2") (pinfunction "2_2") (pintype "passive"))
    )
    (net (code "11") (name "/B") (class "Default")
      (node (ref "R2") (pin "2") (pinfunction "2_2") (pintype "passive"))
      (node (ref "R37") (pin "2") (pinfunction "2_2") (pintype "passive"))
      (node (ref "U1") (pin "7") (pinfunction "B_7") (pintype "bidirectional"))
    )
    (net (code "12") (name "/CAN1_RX") (class "Default")
      (node (ref "IC2") (pin "2") (pinfunction "RXD_2") (pintype "input"))
      (node (ref "U$1") (pin "24") (pinfunction "C5_24") (pintype "bidirectional"))
      (node (ref "U5") (pin "4") (pinfunction "RXD_4") (pintype "bidirectional"))
    )
    (net (code "13") (name "/CAN1_TX") (class "Default")
      (node (ref "IC2") (pin "3") (pinfunction "TXD_3") (pintype "input"))
      (node (ref "U$1") (pin "23") (pinfunction "C4_23") (pintype "bidirectional"))
      (node (ref "U5") (pin "1") (pinfunction "TXD_1") (pintype "bidirectional"))
    )
    (net (code "14") (name "/CAN2_INT") (class "Default")
      (node (ref "U$1") (pin "5") (pinfunction "WKP_5") (pintype "bidirectional"))
      (node (ref "U2") (pin "12") (pinfunction "INT_12") (pintype "output"))
    )
    (net (code "15") (name "/CAN2_RST") (class "Default")
      (node (ref "U$14") (pin "2") (pinfunction "2_2") (pintype "passive"))
      (node (ref "U2") (pin "17") (pinfunction "RESET_17") (pintype "input"))
    )
    (net (code "16") (name "/CAN2_RX") (class "Default")
      (node (ref "U2") (pin "2") (pinfunction "RXCAN_2") (pintype "input"))
      (node (ref "U4") (pin "4") (pinfunction "RXD_4") (pintype "bidirectional"))
    )
    (net (code "17") (name "/CAN2_TX") (class "Default")
      (node (ref "U2") (pin "1") (pinfunction "TXCAN_1") (pintype "output"))
      (node (ref "U4") (pin "1") (pinfunction "TXD_1") (pintype "bidirectional"))
    )
    (net (code "18") (name "/CANH1") (class "Default")
      (node (ref "D10") (pin "1") (pinfunction "1_1") (pintype "passive"))
      (node (ref "IC2") (pin "7") (pinfunction "CANH_7") (pintype "input"))
      (node (ref "R16") (pin "2") (pinfunction "2_2") (pintype "passive"))
      (node (ref "R3") (pin "2") (pinfunction "2_2") (pintype "passive"))
      (node (ref "U5") (pin "7") (pinfunction "CANH_7") (pintype "bidirectional"))
      (node (ref "X5") (pin "P$2") (pinfunction "2_P$2") (pintype "passive"))
    )
    (net (code "19") (name "/CANH2") (class "Default")
      (node (ref "D11") (pin "1") (pinfunction "1_1") (pintype "passive"))
      (node (ref "R22") (pin "2") (pinfunction "2_2") (pintype "passive"))
      (node (ref "R4") (pin "2") (pinfunction "2_2") (pintype "passive"))
      (node (ref "U4") (pin "7") (pinfunction "CANH_7") (pintype "bidirectional"))
      (node (ref "X6") (pin "P$2") (pinfunction "2_P$2") (pintype "passive"))
    )
    (net (code "20") (name "/CANL1") (class "Default")
      (node (ref "D10") (pin "2") (pinfunction "2_2") (pintype "passive"))
      (node (ref "IC2") (pin "6") (pinfunction "CANL_6") (pintype "input"))
      (node (ref "JP2") (pin "1") (pinfunction "1_1") (pintype "passive"))
      (node (ref "R17") (pin "2") (pinfunction "2_2") (pintype "passive"))
      (node (ref "U5") (pin "6") (pinfunction "CANL_6") (pintype "bidirectional"))
      (node (ref "X5") (pin "P$3") (pinfunction "3_P$3") (pintype "passive"))
    )
    (net (code "21") (name "/CANL2") (class "Default")
      (node (ref "D11") (pin "2") (pinfunction "2_2") (pintype "passive"))
      (node (ref "JP3") (pin "1") (pinfunction "1_1") (pintype "passive"))
      (node (ref "R23") (pin "2") (pinfunction "2_2") (pintype "passive"))
      (node (ref "U4") (pin "6") (pinfunction "CANL_6") (pintype "bidirectional"))
      (node (ref "X6") (pin "P$3") (pinfunction "3_P$3") (pintype "passive"))
    )
    (net (code "22") (name "/DAC") (class "Default")
      (node (ref "U$1") (pin "6") (pinfunction "DAC_6") (pintype "bidirectional"))
    )
    (net (code "23") (name "/DE|~{RE}") (class "Default")
      (node (ref "JP11") (pin "2") (pinfunction "2_2") (pintype "passive"))
      (node (ref "U$1") (pin "20") (pinfunction "C1_20") (pintype "bidirectional"))
      (node (ref "U1") (pin "2") (pinfunction "/RE_2") (pintype "bidirectional"))
      (node (ref "U1") (pin "3") (pinfunction "DE_3") (pintype "bidirectional"))
    )
    (net (code "24") (name "/DI") (class "Default")
      (node (ref "JP11") (pin "4") (pinfunction "4_4") (pintype "passive"))
      (node (ref "U$1") (pin "22") (pinfunction "C3_22") (pintype "bidirectional"))
      (node (ref "U1") (pin "4") (pinfunction "DI_4") (pintype "bidirectional"))
    )
    (net (code "25") (name "/GPS_PPS") (class "Default")
      (node (ref "X9") (pin "P$6") (pinfunction "6_P$6") (pintype "passive"))
    )
    (net (code "26") (name "/GPS_PWR_EN") (class "Default")
      (node (ref "JP11") (pin "13") (pinfunction "13_13") (pintype "passive"))
      (node (ref "U$1") (pin "31") (pinfunction "D6_31") (pintype "bidirectional"))
      (node (ref "X9") (pin "P$1") (pinfunction "1_P$1") (pintype "passive"))
    )
    (net (code "27") (name "/GPS_RXD") (class "Default")
      (node (ref "JP10") (pin "3") (pinfunction "3_3") (pintype "passive"))
      (node (ref "U$1") (pin "3") (pinfunction "TX_3") (pintype "bidirectional"))
      (node (ref "X9") (pin "P$3") (pinfunction "3_P$3") (pintype "passive"))
    )
    (net (code "28") (name "/GPS_TXD") (class "Default")
      (node (ref "JP10") (pin "4") (pinfunction "4_4") (pintype "passive"))
      (node (ref "U$1") (pin "4") (pinfunction "RX_4") (pintype "bidirectional"))
      (node (ref "X9") (pin "P$4") (pinfunction "4_P$4") (pintype "passive"))
    )
    (net (code "29") (name "/INTB") (class "Default")
      (node (ref "IC1") (pin "19") (pinfunction "INTB_19") (pintype "output"))
      (node (ref "U$1") (pin "18") (pinfunction "B0_18") (pintype "bidirectional"))
    )
    (net (code "30") (name "/LEDO1") (class "Default")
      (node (ref "IC1") (pin "25") (pinfunction "GPA4_25") (pintype "bidirectional"))
      (node (ref "R13") (pin "2") (pinfunction "2_2") (pintype "passive"))
    )
    (net (code "31") (name "/LEDO2") (class "Default")
      (node (ref "IC1") (pin "26") (pinfunction "GPA5_26") (pintype "bidirectional"))
      (node (ref "R14") (pin "2") (pinfunction "2_2") (pintype "passive"))
    )
    (net (code "32") (name "/LEDO3") (class "Default")
      (node (ref "IC1") (pin "27") (pinfunction "GPA6_27") (pintype "bidirectional"))
      (node (ref "R15") (pin "2") (pinfunction "2_2") (pintype "passive"))
    )
    (net (code "33") (name "/MISO") (class "Default")
      (node (ref "JP10") (pin "8") (pinfunction "8_8") (pintype "passive"))
      (node (ref "SD1") (pin "7") (pinfunction "DO_7") (pintype "bidirectional"))
      (node (ref "U$1") (pin "8") (pinfunction "A4_8") (pintype "bidirectional"))
    )
    (net (code "34") (name "/MISO1") (class "Default")
      (node (ref "U$1") (pin "28") (pinfunction "D3_28") (pintype "bidirectional"))
      (node (ref "U2") (pin "15") (pinfunction "SO_15") (pintype "output"))
    )
    (net (code "35") (name "/MOSI") (class "Default")
      (node (ref "JP10") (pin "7") (pinfunction "7_7") (pintype "passive"))
      (node (ref "SD1") (pin "3") (pinfunction "DI_3") (pintype "bidirectional"))
      (node (ref "U$1") (pin "7") (pinfunction "A5_7") (pintype "bidirectional"))
    )
    (net (code "36") (name "/MOSI1") (class "Default")
      (node (ref "U$1") (pin "27") (pinfunction "D2_27") (pintype "bidirectional"))
      (node (ref "U2") (pin "14") (pinfunction "SI_14") (pintype "input"))
    )
    (net (code "37") (name "/RELAY1") (class "Default")
      (node (ref "IC1") (pin "21") (pinfunction "GPA0_21") (pintype "bidirectional"))
      (node (ref "R5") (pin "2") (pinfunction "2_2") (pintype "passive"))
    )
    (net (code "38") (name "/RELAY2") (class "Default")
      (node (ref "IC1") (pin "22") (pinfunction "GPA1_22") (pintype "bidirectional"))
      (node (ref "R7") (pin "2") (pinfunction "2_2") (pintype "passive"))
    )
    (net (code "39") (name "/RELAY3") (class "Default")
      (node (ref "IC1") (pin "23") (pinfunction "GPA2_23") (pintype "bidirectional"))
      (node (ref "R9") (pin "2") (pinfunction "2_2") (pintype "passive"))
    )
    (net (code "40") (name "/RELAY4") (class "Default")
      (node (ref "IC1") (pin "24") (pinfunction "GPA3_24") (pintype "bidirectional"))
      (node (ref "R11") (pin "2") (pinfunction "2_2") (pintype "passive"))
    )
    (net (code "41") (name "/RO") (class "Default")
      (node (ref "JP11") (pin "3") (pinfunction "3_3") (pintype "passive"))
      (node (ref "U$1") (pin "21") (pinfunction "C2_21") (pintype "bidirectional"))
      (node (ref "U1") (pin "1") (pinfunction "RO_1") (pintype "bidirectional"))
    )
    (net (code "42") (name "/SCK") (class "Default")
      (node (ref "JP10") (pin "9") (pinfunction "9_9") (pintype "passive"))
      (node (ref "SD1") (pin "5") (pinfunction "SCLK_5") (pintype "bidirectional"))
      (node (ref "U$1") (pin "9") (pinfunction "A3_9") (pintype "bidirectional"))
    )
    (net (code "43") (name "/SCK1") (class "Default")
      (node (ref "U$1") (pin "29") (pinfunction "D4_29") (pintype "bidirectional"))
      (node (ref "U2") (pin "13") (pinfunction "SCK_13") (pintype "input"))
    )
    (net (code "44") (name "/SCL") (class "Default")
      (node (ref "IC1") (pin "12") (pinfunction "SCL_12") (pintype "input"))
      (node (ref "JP11") (pin "8") (pinfunction "8_8") (pintype "passive"))
      (node (ref "R19") (pin "1") (pinfunction "1_1") (pintype "passive"))
      (node (ref "U$1") (pin "26") (pinfunction "D1_26") (pintype "bidirectional"))
      (node (ref "U6") (pin "5") (pinfunction "SCL_5") (pintype "bidirectional"))
    )
    (net (code "45") (name "/SDA") (class "Default")
      (node (ref "IC1") (pin "13") (pinfunction "SDA_13") (pintype "bidirectional"))
      (node (ref "JP11") (pin "7") (pinfunction "7_7") (pintype "passive"))
      (node (ref "R20") (pin "1") (pinfunction "1_1") (pintype "passive"))
      (node (ref "U$1") (pin "25") (pinfunction "D0_25") (pintype "bidirectional"))
      (node (ref "U6") (pin "4") (pinfunction "SDA_4") (pintype "bidirectional"))
    )
    (net (code "46") (name "/SS") (class "Default")
      (node (ref "SD1") (pin "2") (pinfunction "CS_2") (pintype "bidirectional"))
      (node (ref "U$1") (pin "10") (pinfunction "A2_10") (pintype "bidirectional"))
    )
    (net (code "47") (name "/SS1") (class "Default")
      (node (ref "U$1") (pin "30") (pinfunction "D5_30") (pintype "bidirectional"))
      (node (ref "U2") (pin "16") (pinfunction "CS_16") (pintype "input"))
    )
    (net (code "48") (name "/SWT0") (class "Default")
      (node (ref "C20") (pin "1") (pinfunction "1_1") (pintype "passive"))
      (node (ref "D15") (pin "3") (pinfunction "3_3") (pintype "bidirectional"))
      (node (ref "IC1") (pin "1") (pinfunction "GPB0_1") (pintype "bidirectional"))
      (node (ref "R24") (pin "2") (pinfunction "2_2") (pintype "passive"))
      (node (ref "R31") (pin "1") (pinfunction "1_1") (pintype "passive"))
    )
    (net (code "49") (name "/SWT1") (class "Default")
      (node (ref "C19") (pin "1") (pinfunction "1_1") (pintype "passive"))
      (node (ref "D14") (pin "3") (pinfunction "3_3") (pintype "bidirectional"))
      (node (ref "IC1") (pin "2") (pinfunction "GPB1_2") (pintype "bidirectional"))
      (node (ref "R25") (pin "2") (pinfunction "2_2") (pintype "passive"))
      (node (ref "R30") (pin "1") (pinfunction "1_1") (pintype "passive"))
    )
    (net (code "50") (name "/SWT2") (class "Default")
      (node (ref "C18") (pin "1") (pinfunction "1_1") (pintype "passive"))
      (node (ref "D13") (pin "3") (pinfunction "3_3") (pintype "bidirectional"))
      (node (ref "IC1") (pin "3") (pinfunction "GPB2_3") (pintype "bidirectional"))
      (node (ref "R26") (pin "2") (pinfunction "2_2") (pintype "passive"))
      (node (ref "R29") (pin "1") (pinfunction "1_1") (pintype "passive"))
    )
    (net (code "51") (name "/SWT3") (class "Default")
      (node (ref "C17") (pin "1") (pinfunction "1_1") (pintype "passive"))
      (node (ref "D12") (pin "3") (pinfunction "3_3") (pintype "bidirectional"))
      (node (ref "IC1") (pin "4") (pinfunction "GPB3_4") (pintype "bidirectional"))
      (node (ref "R27") (pin "2") (pinfunction "2_2") (pintype "passive"))
      (node (ref "R28") (pin "1") (pinfunction "1_1") (pintype "passive"))
    )
    (net (code "52") (name "GND") (class "Default")
      (node (ref "C1") (pin "1") (pinfunction "1_1") (pintype "passive"))
      (node (ref "C12") (pin "1") (pinfunction "1_1") (pintype "passive"))
      (node (ref "C13") (pin "1") (pinfunction "1_1") (pintype "passive"))
      (node (ref "C14") (pin "1") (pinfunction "1_1") (pintype "passive"))
      (node (ref "C15") (pin "1") (pinfunction "1_1") (pintype "passive"))
      (node (ref "C16") (pin "1") (pinfunction "1_1") (pintype "passive"))
      (node (ref "C17") (pin "2") (pinfunction "2_2") (pintype "passive"))
      (node (ref "C18") (pin "2") (pinfunction "2_2") (pintype "passive"))
      (node (ref "C19") (pin "2") (pinfunction "2_2") (pintype "passive"))
      (node (ref "C2") (pin "1") (pinfunction "1_1") (pintype "passive"))
      (node (ref "C20") (pin "2") (pinfunction "2_2") (pintype "passive"))
      (node (ref "C21") (pin "1") (pinfunction "1_1") (pintype "passive"))
      (node (ref "C22") (pin "+") (pinfunction "+_+") (pintype "passive"))
      (node (ref "C23") (pin "2") (pinfunction "2_2") (pintype "passive"))
      (node (ref "C24") (pin "2") (pinfunction "2_2") (pintype "passive"))
      (node (ref "C3") (pin "1") (pinfunction "1_1") (pintype "passive"))
      (node (ref "C4") (pin "1") (pinfunction "1_1") (pintype "passive"))
      (node (ref "C5") (pin "1") (pinfunction "1_1") (pintype "passive"))
      (node (ref "C6") (pin "1") (pinfunction "1_1") (pintype "passive"))
      (node (ref "C7") (pin "1") (pinfunction "1_1") (pintype "passive"))
      (node (ref "C9") (pin "1") (pinfunction "1_1") (pintype "passive"))
      (node (ref "CT1") (pin "-") (pinfunction "-_-") (pintype "passive"))
      (node (ref "CT2") (pin "-") (pinfunction "-_-") (pintype "passive"))
      (node (ref "D1") (pin "-") (pinfunction "-_-") (pintype "passive"))
      (node (ref "D11") (pin "3") (pinfunction "3_3") (pintype "passive"))
      (node (ref "D12") (pin "2") (pinfunction "2_2") (pintype "power_in"))
      (node (ref "D13") (pin "2") (pinfunction "2_2") (pintype "power_in"))
      (node (ref "D14") (pin "2") (pinfunction "2_2") (pintype "power_in"))
      (node (ref "D15") (pin "2") (pinfunction "2_2") (pintype "power_in"))
      (node (ref "D16") (pin "2") (pinfunction "2_2") (pintype "power_in"))
      (node (ref "D18") (pin "3") (pinfunction "3_3") (pintype "passive"))
      (node (ref "IC1") (pin "10") (pinfunction "VSS_10") (pintype "power_in"))
      (node (ref "IC2") (pin "4") (pinfunction "GND1_4") (pintype "input"))
      (node (ref "JP10") (pin "2") (pinfunction "2_2") (pintype "passive"))
      (node (ref "JP11") (pin "15") (pinfunction "15_15") (pintype "passive"))
      (node (ref "JP4") (pin "3") (pinfunction "3_3") (pintype "passive"))
      (node (ref "JP5") (pin "3") (pinfunction "3_3") (pintype "passive"))
      (node (ref "JP6") (pin "3") (pinfunction "3_3") (pintype "passive"))
      (node (ref "JP7") (pin "1") (pinfunction "1_1") (pintype "passive"))
      (node (ref "JP9") (pin "3") (pinfunction "3_3") (pintype "passive"))
      (node (ref "R34") (pin "1") (pinfunction "1_1") (pintype "passive"))
      (node (ref "R35") (pin "1") (pinfunction "1_1") (pintype "passive"))
      (node (ref "SD1") (pin "6") (pinfunction "VSS_6") (pintype "bidirectional"))
      (node (ref "SD1") (pin "G1") (pinfunction "G1_G1") (pintype "bidirectional"))
      (node (ref "SD1") (pin "G2") (pinfunction "G2_G2") (pintype "bidirectional"))
      (node (ref "SD1") (pin "G3") (pinfunction "G3_G3") (pintype "bidirectional"))
      (node (ref "SD1") (pin "G4") (pinfunction "G4_G4") (pintype "bidirectional"))
      (node (ref "U$1") (pin "2") (pinfunction "GND_2") (pintype "power_in"))
      (node (ref "U$1") (pin "33") (pinfunction "GND_33") (pintype "power_in"))
      (node (ref "U$10") (pin "2") (pinfunction "E_2") (pintype "passive"))
      (node (ref "U$11") (pin "1") (pinfunction "1_1") (pintype "passive"))
      (node (ref "U$12") (pin "2") (pinfunction "E_2") (pintype "passive"))
      (node (ref "U$17") (pin "1") (pinfunction "1_1") (pintype "passive"))
      (node (ref "U$4") (pin "1") (pinfunction "1_1") (pintype "passive"))
      (node (ref "U$5") (pin "1") (pinfunction "1_1") (pintype "passive"))
      (node (ref "U$6") (pin "2") (pinfunction "E_2") (pintype "passive"))
      (node (ref "U$7") (pin "1") (pinfunction "1_1") (pintype "passive"))
      (node (ref "U$8") (pin "2") (pinfunction "E_2") (pintype "passive"))
      (node (ref "U$9") (pin "1") (pinfunction "1_1") (pintype "passive"))
      (node (ref "U1") (pin "5") (pinfunction "GND_5") (pintype "bidirectional"))
      (node (ref "U2") (pin "9") (pinfunction "VSS_9") (pintype "power_in"))
      (node (ref "U3") (pin "2") (pinfunction "VIN-_2") (pintype "bidirectional"))
      (node (ref "U4") (pin "2") (pinfunction "VSS_2") (pintype "bidirectional"))
      (node (ref "U5") (pin "2") (pinfunction "VSS_2") (pintype "bidirectional"))
      (node (ref "U6") (pin "2") (pinfunction "VSS_2") (pintype "bidirectional"))
      (node (ref "X10") (pin "P$3") (pinfunction "3_P$3") (pintype "passive"))
      (node (ref "X11") (pin "P$2") (pinfunction "2_P$2") (pintype "passive"))
      (node (ref "X2") (pin "P$3") (pinfunction "3_P$3") (pintype "passive"))
      (node (ref "X3") (pin "P$2") (pinfunction "2_P$2") (pintype "passive"))
      (node (ref "X4") (pin "P$1") (pinfunction "1_P$1") (pintype "passive"))
      (node (ref "X4") (pin "P$2") (pinfunction "2_P$2") (pintype "passive"))
      (node (ref "X4") (pin "P$3") (pinfunction "3_P$3") (pintype "passive"))
      (node (ref "X6") (pin "P$1") (pinfunction "1_P$1") (pintype "passive"))
      (node (ref "X7") (pin "P$2") (pinfunction "2_P$2") (pintype "passive"))
      (node (ref "X8") (pin "P$2") (pinfunction "2_P$2") (pintype "passive"))
      (node (ref "X9") (pin "P$2") (pinfunction "2_P$2") (pintype "passive"))
      (node (ref "Y1") (pin "2") (pinfunction "2_2") (pintype "passive"))
    )
    (net (code "53") (name "GND-ISO") (class "Default")
      (node (ref "C8") (pin "1") (pinfunction "1_1") (pintype "passive"))
      (node (ref "IC2") (pin "5") (pinfunction "GND2_5") (pintype "input"))
      (node (ref "JP7") (pin "3") (pinfunction "3_3") (pintype "passive"))
      (node (ref "U3") (pin "4") (pinfunction "VOUT-_4") (pintype "bidirectional"))
    )
    (net (code "54") (name "Net-(C10-Pad2)") (class "Default")
      (node (ref "C10") (pin "2") (pinfunction "2_2") (pintype "passive"))
      (node (ref "R16") (pin "1") (pinfunction "1_1") (pintype "passive"))
    )
    (net (code "55") (name "Net-(C11-Pad2)") (class "Default")
      (node (ref "C11") (pin "2") (pinfunction "2_2") (pintype "passive"))
      (node (ref "R17") (pin "1") (pinfunction "1_1") (pintype "passive"))
    )
    (net (code "56") (name "Net-(C15-Pad2)") (class "Default")
      (node (ref "C15") (pin "2") (pinfunction "2_2") (pintype "passive"))
      (node (ref "R22") (pin "1") (pinfunction "1_1") (pintype "passive"))
    )
    (net (code "57") (name "Net-(C16-Pad2)") (class "Default")
      (node (ref "C16") (pin "2") (pinfunction "2_2") (pintype "passive"))
      (node (ref "R23") (pin "1") (pinfunction "1_1") (pintype "passive"))
    )
    (net (code "58") (name "Net-(D1-Pad+)") (class "Default")
      (node (ref "D1") (pin "+") (pinfunction "+_+") (pintype "passive"))
      (node (ref "R1") (pin "1") (pinfunction "1_1") (pintype "passive"))
    )
    (net (code "59") (name "Net-(D3-Pad+)") (class "Default")
      (node (ref "D3") (pin "+") (pinfunction "+_+") (pintype "passive"))
      (node (ref "R6") (pin "2") (pinfunction "2_2") (pintype "passive"))
    )
    (net (code "60") (name "Net-(D5-Pad+)") (class "Default")
      (node (ref "D5") (pin "+") (pinfunction "+_+") (pintype "passive"))
      (node (ref "R8") (pin "2") (pinfunction "2_2") (pintype "passive"))
    )
    (net (code "61") (name "Net-(D7-Pad+)") (class "Default")
      (node (ref "D7") (pin "+") (pinfunction "+_+") (pintype "passive"))
      (node (ref "R10") (pin "2") (pinfunction "2_2") (pintype "passive"))
    )
    (net (code "62") (name "Net-(D9-Pad+)") (class "Default")
      (node (ref "D9") (pin "+") (pinfunction "+_+") (pintype "passive"))
      (node (ref "R12") (pin "2") (pinfunction "2_2") (pintype "passive"))
    )
    (net (code "63") (name "Net-(D17-PadC)") (class "Default")
      (node (ref "D17") (pin "C") (pinfunction "C_C") (pintype "passive"))
      (node (ref "F3") (pin "1") (pinfunction "1_1") (pintype "passive"))
    )
    (net (code "64") (name "Net-(J1-Pad1)") (class "Default")
      (node (ref "J1") (pin "1") (pinfunction "1_1") (pintype "passive"))
      (node (ref "K1") (pin "S") (pinfunction "S_S") (pintype "passive"))
    )
    (net (code "65") (name "Net-(J1-Pad2)") (class "Default")
      (node (ref "J1") (pin "2") (pinfunction "2_2") (pintype "passive"))
      (node (ref "K1") (pin "P") (pinfunction "P_P") (pintype "passive"))
    )
    (net (code "66") (name "Net-(J1-Pad3)") (class "Default")
      (node (ref "J1") (pin "3") (pinfunction "3_3") (pintype "passive"))
      (node (ref "K1") (pin "O") (pinfunction "O_O") (pintype "passive"))
    )
    (net (code "67") (name "Net-(J2-Pad1)") (class "Default")
      (node (ref "J2") (pin "1") (pinfunction "1_1") (pintype "passive"))
      (node (ref "K2") (pin "S") (pinfunction "S_S") (pintype "passive"))
    )
    (net (code "68") (name "Net-(J2-Pad2)") (class "Default")
      (node (ref "J2") (pin "2") (pinfunction "2_2") (pintype "passive"))
      (node (ref "K2") (pin "P") (pinfunction "P_P") (pintype "passive"))
    )
    (net (code "69") (name "Net-(J2-Pad3)") (class "Default")
      (node (ref "J2") (pin "3") (pinfunction "3_3") (pintype "passive"))
      (node (ref "K2") (pin "O") (pinfunction "O_O") (pintype "passive"))
    )
    (net (code "70") (name "Net-(J3-Pad1)") (class "Default")
      (node (ref "J3") (pin "1") (pinfunction "1_1") (pintype "passive"))
      (node (ref "K3") (pin "S") (pinfunction "S_S") (pintype "passive"))
    )
    (net (code "71") (name "Net-(J3-Pad2)") (class "Default")
      (node (ref "J3") (pin "2") (pinfunction "2_2") (pintype "passive"))
      (node (ref "K3") (pin "P") (pinfunction "P_P") (pintype "passive"))
    )
    (net (code "72") (name "Net-(J3-Pad3)") (class "Default")
      (node (ref "J3") (pin "3") (pinfunction "3_3") (pintype "passive"))
      (node (ref "K3") (pin "O") (pinfunction "O_O") (pintype "passive"))
    )
    (net (code "73") (name "Net-(J4-Pad1)") (class "Default")
      (node (ref "J4") (pin "1") (pinfunction "1_1") (pintype "passive"))
      (node (ref "K4") (pin "S") (pinfunction "S_S") (pintype "passive"))
    )
    (net (code "74") (name "Net-(J4-Pad2)") (class "Default")
      (node (ref "J4") (pin "2") (pinfunction "2_2") (pintype "passive"))
      (node (ref "K4") (pin "P") (pinfunction "P_P") (pintype "passive"))
    )
    (net (code "75") (name "Net-(J4-Pad3)") (class "Default")
      (node (ref "J4") (pin "3") (pinfunction "3_3") (pintype "passive"))
      (node (ref "K4") (pin "O") (pinfunction "O_O") (pintype "passive"))
    )
    (net (code "76") (name "Net-(JP1-Pad1)") (class "Default")
      (node (ref "JP1") (pin "1") (pinfunction "1_1") (pintype "passive"))
      (node (ref "R2") (pin "1") (pinfunction "1_1") (pintype "passive"))
    )
    (net (code "77") (name "Net-(JP2-Pad2)") (class "Default")
      (node (ref "JP2") (pin "2") (pinfunction "2_2") (pintype "passive"))
      (node (ref "R3") (pin "1") (pinfunction "1_1") (pintype "passive"))
    )
    (net (code "78") (name "Net-(JP3-Pad2)") (class "Default")
      (node (ref "JP3") (pin "2") (pinfunction "2_2") (pintype "passive"))
      (node (ref "R4") (pin "1") (pinfunction "1_1") (pintype "passive"))
    )
    (net (code "79") (name "Net-(U$1-3V3)") (class "Default")
      (node (ref "F2") (pin "1") (pinfunction "1_1") (pintype "passive"))
      (node (ref "JP11") (pin "18") (pinfunction "18_18") (pintype "passive"))
      (node (ref "U$1") (pin "36") (pinfunction "3V3_36") (pintype "power_in"))
    )
    (net (code "80") (name "Net-(U$1-VBAT)") (class "Default")
      (node (ref "JP11") (pin "16") (pinfunction "16_16") (pintype "passive"))
      (node (ref "U$1") (pin "34") (pinfunction "VBAT_34") (pintype "power_in"))
    )
    (net (code "81") (name "Net-(U$1-VIN)") (class "Default")
      (node (ref "F1") (pin "1") (pinfunction "1_1") (pintype "passive"))
      (node (ref "JP10") (pin "1") (pinfunction "1_1") (pintype "passive"))
      (node (ref "U$1") (pin "1") (pinfunction "VIN_1") (pintype "power_in"))
    )
    (net (code "82") (name "Net-(U$1-~{RST})") (class "Default")
      (node (ref "JP11") (pin "17") (pinfunction "17_17") (pintype "passive"))
      (node (ref "U$1") (pin "35") (pinfunction "~{RST}_35") (pintype "bidirectional"))
    )
    (net (code "83") (name "Net-(U$6-B)") (class "Default")
      (node (ref "R5") (pin "1") (pinfunction "1_1") (pintype "passive"))
      (node (ref "U$5") (pin "2") (pinfunction "2_2") (pintype "passive"))
      (node (ref "U$6") (pin "1") (pinfunction "B_1") (pintype "passive"))
    )
    (net (code "84") (name "Net-(U$6-C)") (class "Default")
      (node (ref "D2") (pin "+") (pinfunction "+_+") (pintype "passive"))
      (node (ref "D3") (pin "-") (pinfunction "-_-") (pintype "passive"))
      (node (ref "K1") (pin "2") (pinfunction "2_2") (pintype "passive"))
      (node (ref "U$6") (pin "3") (pinfunction "C_3") (pintype "passive"))
    )
    (net (code "85") (name "Net-(U$8-B)") (class "Default")
      (node (ref "R7") (pin "1") (pinfunction "1_1") (pintype "passive"))
      (node (ref "U$7") (pin "2") (pinfunction "2_2") (pintype "passive"))
      (node (ref "U$8") (pin "1") (pinfunction "B_1") (pintype "passive"))
    )
    (net (code "86") (name "Net-(U$8-C)") (class "Default")
      (node (ref "D4") (pin "+") (pinfunction "+_+") (pintype "passive"))
      (node (ref "D5") (pin "-") (pinfunction "-_-") (pintype "passive"))
      (node (ref "K2") (pin "2") (pinfunction "2_2") (pintype "passive"))
      (node (ref "U$8") (pin "3") (pinfunction "C_3") (pintype "passive"))
    )
    (net (code "87") (name "Net-(U$10-B)") (class "Default")
      (node (ref "R9") (pin "1") (pinfunction "1_1") (pintype "passive"))
      (node (ref "U$10") (pin "1") (pinfunction "B_1") (pintype "passive"))
      (node (ref "U$9") (pin "2") (pinfunction "2_2") (pintype "passive"))
    )
    (net (code "88") (name "Net-(U$10-C)") (class "Default")
      (node (ref "D6") (pin "+") (pinfunction "+_+") (pintype "passive"))
      (node (ref "D7") (pin "-") (pinfunction "-_-") (pintype "passive"))
      (node (ref "K3") (pin "2") (pinfunction "2_2") (pintype "passive"))
      (node (ref "U$10") (pin "3") (pinfunction "C_3") (pintype "passive"))
    )
    (net (code "89") (name "Net-(U$12-B)") (class "Default")
      (node (ref "R11") (pin "1") (pinfunction "1_1") (pintype "passive"))
      (node (ref "U$11") (pin "2") (pinfunction "2_2") (pintype "passive"))
      (node (ref "U$12") (pin "1") (pinfunction "B_1") (pintype "passive"))
    )
    (net (code "90") (name "Net-(U$12-C)") (class "Default")
      (node (ref "D8") (pin "+") (pinfunction "+_+") (pintype "passive"))
      (node (ref "D9") (pin "-") (pinfunction "-_-") (pintype "passive"))
      (node (ref "K4") (pin "2") (pinfunction "2_2") (pintype "passive"))
      (node (ref "U$12") (pin "3") (pinfunction "C_3") (pintype "passive"))
    )
    (net (code "91") (name "Net-(U2A-OSC1)") (class "Default")
      (node (ref "R18") (pin "2") (pinfunction "2_2") (pintype "passive"))
      (node (ref "U2") (pin "8") (pinfunction "OSC1_8") (pintype "input"))
      (node (ref "Y1") (pin "1") (pinfunction "1_1") (pintype "passive"))
    )
    (net (code "92") (name "Net-(U2A-OSC2)") (class "Default")
      (node (ref "R18") (pin "1") (pinfunction "1_1") (pintype "passive"))
      (node (ref "U2") (pin "7") (pinfunction "OSC2_7") (pintype "output"))
      (node (ref "Y1") (pin "3") (pinfunction "3_3") (pintype "passive"))
    )
    (net (code "93") (name "Net-(U4-RS)") (class "Default")
      (node (ref "U$17") (pin "2") (pinfunction "2_2") (pintype "passive"))
      (node (ref "U4") (pin "8") (pinfunction "RS_8") (pintype "bidirectional"))
    )
    (net (code "94") (name "Net-(U5-RS)") (class "Default")
      (node (ref "U$4") (pin "2") (pinfunction "2_2") (pintype "passive"))
      (node (ref "U5") (pin "8") (pinfunction "RS_8") (pintype "bidirectional"))
    )
    (net (code "95") (name "Net-(U6-AO)") (class "Default")
      (node (ref "JP9") (pin "2") (pinfunction "2_2") (pintype "passive"))
      (node (ref "U6") (pin "6") (pinfunction "AO_6") (pintype "bidirectional"))
    )
    (net (code "96") (name "Net-(X1-1)") (class "Default")
      (node (ref "R27") (pin "1") (pinfunction "1_1") (pintype "passive"))
      (node (ref "X1") (pin "P$1") (pinfunction "1_P$1") (pintype "passive"))
    )
    (net (code "97") (name "Net-(X1-2)") (class "Default")
      (node (ref "R24") (pin "1") (pinfunction "1_1") (pintype "passive"))
      (node (ref "X1") (pin "P$2") (pinfunction "2_P$2") (pintype "passive"))
    )
    (net (code "98") (name "Net-(X1-3)") (class "Default")
      (node (ref "R26") (pin "1") (pinfunction "1_1") (pintype "passive"))
      (node (ref "X1") (pin "P$3") (pinfunction "3_P$3") (pintype "passive"))
    )
    (net (code "99") (name "Net-(X1-4)") (class "Default")
      (node (ref "R25") (pin "1") (pinfunction "1_1") (pintype "passive"))
      (node (ref "X1") (pin "P$4") (pinfunction "4_P$4") (pintype "passive"))
    )
    (net (code "100") (name "Net-(X3-1)") (class "Default")
      (node (ref "D17") (pin "A") (pinfunction "A_A") (pintype "passive"))
      (node (ref "X3") (pin "P$1") (pinfunction "1_P$1") (pintype "passive"))
    )
    (net (code "101") (name "Net-(X4-4)") (class "Default")
      (node (ref "R13") (pin "1") (pinfunction "1_1") (pintype "passive"))
      (node (ref "X4") (pin "P$4") (pinfunction "4_P$4") (pintype "passive"))
    )
    (net (code "102") (name "Net-(X4-5)") (class "Default")
      (node (ref "R14") (pin "1") (pinfunction "1_1") (pintype "passive"))
      (node (ref "X4") (pin "P$5") (pinfunction "5_P$5") (pintype "passive"))
    )
    (net (code "103") (name "Net-(X4-6)") (class "Default")
      (node (ref "R15") (pin "1") (pinfunction "1_1") (pintype "passive"))
      (node (ref "X4") (pin "P$6") (pinfunction "6_P$6") (pintype "passive"))
    )
    (net (code "104") (name "Net-(X5-1)") (class "Default")
      (node (ref "C10") (pin "1") (pinfunction "1_1") (pintype "passive"))
      (node (ref "C11") (pin "1") (pinfunction "1_1") (pintype "passive"))
      (node (ref "D10") (pin "3") (pinfunction "3_3") (pintype "passive"))
      (node (ref "JP7") (pin "2") (pinfunction "2_2") (pintype "passive"))
      (node (ref "X5") (pin "P$1") (pinfunction "1_P$1") (pintype "passive"))
    )
    (net (code "105") (name "Net-(X7-1)") (class "Default")
      (node (ref "R32") (pin "2") (pinfunction "2_2") (pintype "passive"))
      (node (ref "X7") (pin "P$1") (pinfunction "1_P$1") (pintype "passive"))
    )
    (net (code "106") (name "Net-(X8-1)") (class "Default")
      (node (ref "R33") (pin "2") (pinfunction "2_2") (pintype "passive"))
      (node (ref "X8") (pin "P$1") (pinfunction "1_P$1") (pintype "passive"))
    )
    (net (code "107") (name "Net-(X11-1)") (class "Default")
      (node (ref "F4") (pin "2") (pinfunction "2_2") (pintype "passive"))
      (node (ref "X11") (pin "P$1") (pinfunction "1_P$1") (pintype "passive"))
    )
    (net (code "108") (name "Net-(X11-3)") (class "Default")
      (node (ref "D18") (pin "1") (pinfunction "1_1") (pintype "passive"))
      (node (ref "R36") (pin "2") (pinfunction "2_2") (pintype "passive"))
      (node (ref "X11") (pin "P$3") (pinfunction "3_P$3") (pintype "passive"))
    )
    (net (code "109") (name "Net-(X11-4)") (class "Default")
      (node (ref "D18") (pin "2") (pinfunction "2_2") (pintype "passive"))
      (node (ref "R37") (pin "1") (pinfunction "1_1") (pintype "passive"))
      (node (ref "X11") (pin "P$4") (pinfunction "4_P$4") (pintype "passive"))
    )
    (net (code "110") (name "VCC-ISO") (class "Default")
      (node (ref "C8") (pin "2") (pinfunction "2_2") (pintype "passive"))
      (node (ref "IC2") (pin "8") (pinfunction "VCC2_8") (pintype "input"))
      (node (ref "U3") (pin "6") (pinfunction "VOUT+_6") (pintype "bidirectional"))
    )
    (net (code "111") (name "VDD") (class "Default")
      (node (ref "C1") (pin "2") (pinfunction "2_2") (pintype "passive"))
      (node (ref "C12") (pin "2") (pinfunction "2_2") (pintype "passive"))
      (node (ref "C2") (pin "2") (pinfunction "2_2") (pintype "passive"))
      (node (ref "C3") (pin "2") (pinfunction "2_2") (pintype "passive"))
      (node (ref "C4") (pin "2") (pinfunction "2_2") (pintype "passive"))
      (node (ref "C6") (pin "2") (pinfunction "2_2") (pintype "passive"))
      (node (ref "F2") (pin "2") (pinfunction "2_2") (pintype "passive"))
      (node (ref "IC2") (pin "1") (pinfunction "VCC1_1") (pintype "input"))
      (node (ref "SD1") (pin "4") (pinfunction "VDD_4") (pintype "bidirectional"))
      (node (ref "U$14") (pin "1") (pinfunction "1_1") (pintype "passive"))
      (node (ref "U1") (pin "8") (pinfunction "VCC_8") (pintype "bidirectional"))
      (node (ref "U2") (pin "18") (pinfunction "VDD_18") (pintype "power_in"))
      (node (ref "U4") (pin "5") (pinfunction "VREF_5") (pintype "bidirectional"))
      (node (ref "U5") (pin "5") (pinfunction "VREF_5") (pintype "bidirectional"))
    )
    (net (code "112") (name "unconnected-(IC1-GPA7-Pad28)") (class "Default")
      (node (ref "IC1") (pin "28") (pinfunction "GPA7_28") (pintype "bidirectional"))
    )
    (net (code "113") (name "unconnected-(IC1-GPB4-Pad5)") (class "Default")
      (node (ref "IC1") (pin "5") (pinfunction "GPB4_5") (pintype "bidirectional"))
    )
    (net (code "114") (name "unconnected-(IC1-GPB5-Pad6)") (class "Default")
      (node (ref "IC1") (pin "6") (pinfunction "GPB5_6") (pintype "bidirectional"))
    )
    (net (code "115") (name "unconnected-(IC1-GPB6-Pad7)") (class "Default")
      (node (ref "IC1") (pin "7") (pinfunction "GPB6_7") (pintype "bidirectional"))
    )
    (net (code "116") (name "unconnected-(IC1-GPB7-Pad8)") (class "Default")
      (node (ref "IC1") (pin "8") (pinfunction "GPB7_8") (pintype "bidirectional"))
    )
    (net (code "117") (name "unconnected-(IC1-INTA-Pad20)") (class "Default")
      (node (ref "IC1") (pin "20") (pinfunction "INTA_20") (pintype "output"))
    )
    (net (code "118") (name "unconnected-(JP10-Pad6)") (class "Default")
      (node (ref "JP10") (pin "6") (pinfunction "6_6") (pintype "passive"))
    )
    (net (code "119") (name "unconnected-(JP10-Pad10)") (class "Default")
      (node (ref "JP10") (pin "10") (pinfunction "10_10") (pintype "passive"))
    )
    (net (code "120") (name "unconnected-(JP10-Pad13)") (class "Default")
      (node (ref "JP10") (pin "13") (pinfunction "13_13") (pintype "passive"))
    )
    (net (code "121") (name "unconnected-(JP10-Pad14)") (class "Default")
      (node (ref "JP10") (pin "14") (pinfunction "14_14") (pintype "passive"))
    )
    (net (code "122") (name "unconnected-(JP10-Pad15)") (class "Default")
      (node (ref "JP10") (pin "15") (pinfunction "15_15") (pintype "passive"))
    )
    (net (code "123") (name "unconnected-(JP10-Pad16)") (class "Default")
      (node (ref "JP10") (pin "16") (pinfunction "16_16") (pintype "passive"))
    )
    (net (code "124") (name "unconnected-(JP10-Pad17)") (class "Default")
      (node (ref "JP10") (pin "17") (pinfunction "17_17") (pintype "passive"))
    )
    (net (code "125") (name "unconnected-(JP10-Pad18)") (class "Default")
      (node (ref "JP10") (pin "18") (pinfunction "18_18") (pintype "passive"))
    )
    (net (code "126") (name "unconnected-(JP11-Pad5)") (class "Default")
      (node (ref "JP11") (pin "5") (pinfunction "5_5") (pintype "passive"))
    )
    (net (code "127") (name "unconnected-(JP11-Pad6)") (class "Default")
      (node (ref "JP11") (pin "6") (pinfunction "6_6") (pintype "passive"))
    )
    (net (code "128") (name "unconnected-(JP11-Pad9)") (class "Default")
      (node (ref "JP11") (pin "9") (pinfunction "9_9") (pintype "passive"))
    )
    (net (code "129") (name "unconnected-(JP11-Pad10)") (class "Default")
      (node (ref "JP11") (pin "10") (pinfunction "10_10") (pintype "passive"))
    )
    (net (code "130") (name "unconnected-(JP11-Pad11)") (class "Default")
      (node (ref "JP11") (pin "11") (pinfunction "11_11") (pintype "passive"))
    )
    (net (code "131") (name "unconnected-(JP11-Pad12)") (class "Default")
      (node (ref "JP11") (pin "12") (pinfunction "12_12") (pintype "passive"))
    )
    (net (code "132") (name "unconnected-(JP11-Pad14)") (class "Default")
      (node (ref "JP11") (pin "14") (pinfunction "14_14") (pintype "passive"))
    )
    (net (code "133") (name "unconnected-(SD1-CDN-Pad9)") (class "Default")
      (node (ref "SD1") (pin "9") (pinfunction "CDN_9") (pintype "bidirectional"))
    )
    (net (code "134") (name "unconnected-(SD1-DATA1-Pad8)") (class "Default")
      (node (ref "SD1") (pin "8") (pinfunction "DATA1_8") (pintype "bidirectional"))
    )
    (net (code "135") (name "unconnected-(SD1-DATA2-Pad1)") (class "Default")
      (node (ref "SD1") (pin "1") (pinfunction "DATA2_1") (pintype "bidirectional"))
    )
    (net (code "136") (name "unconnected-(U$1-B1-Pad17)") (class "Default")
      (node (ref "U$1") (pin "17") (pinfunction "B1_17") (pintype "bidirectional"))
    )
    (net (code "137") (name "unconnected-(U$1-B2-Pad16)") (class "Default")
      (node (ref "U$1") (pin "16") (pinfunction "B2_16") (pintype "bidirectional"))
    )
    (net (code "138") (name "unconnected-(U$1-B3-Pad15)") (class "Default")
      (node (ref "U$1") (pin "15") (pinfunction "B3_15") (pintype "bidirectional"))
    )
    (net (code "139") (name "unconnected-(U$1-B4-Pad14)") (class "Default")
      (node (ref "U$1") (pin "14") (pinfunction "B4_14") (pintype "bidirectional"))
    )
    (net (code "140") (name "unconnected-(U$1-B5-Pad13)") (class "Default")
      (node (ref "U$1") (pin "13") (pinfunction "B5_13") (pintype "bidirectional"))
    )
    (net (code "141") (name "unconnected-(U$1-D7-Pad32)") (class "Default")
      (node (ref "U$1") (pin "32") (pinfunction "D7_32") (pintype "bidirectional"))
    )
    (net (code "142") (name "unconnected-(U2A-CLKOUT-Pad3)") (class "Default")
      (node (ref "U2") (pin "3") (pinfunction "CLKOUT_3") (pintype "output"))
    )
    (net (code "143") (name "unconnected-(U2A-RX0BF-Pad11)") (class "Default")
      (node (ref "U2") (pin "11") (pinfunction "RX0BF_11") (pintype "output"))
    )
    (net (code "144") (name "unconnected-(U2A-RX1BF-Pad10)") (class "Default")
      (node (ref "U2") (pin "10") (pinfunction "RX1BF_10") (pintype "output"))
    )
    (net (code "145") (name "unconnected-(U2A-TX0RTS-Pad4)") (class "Default")
      (node (ref "U2") (pin "4") (pinfunction "TX0RTS_4") (pintype "input"))
    )
    (net (code "146") (name "unconnected-(U2A-TX1RTS-Pad5)") (class "Default")
      (node (ref "U2") (pin "5") (pinfunction "TX1RTS_5") (pintype "input"))
    )
    (net (code "147") (name "unconnected-(U2A-TX2RTS-Pad6)") (class "Default")
      (node (ref "U2") (pin "6") (pinfunction "TX2RTS_6") (pintype "input"))
    )
  )
)
